# l2-l3.net
KiCad netlist of a schematic drawn in Altium Designer
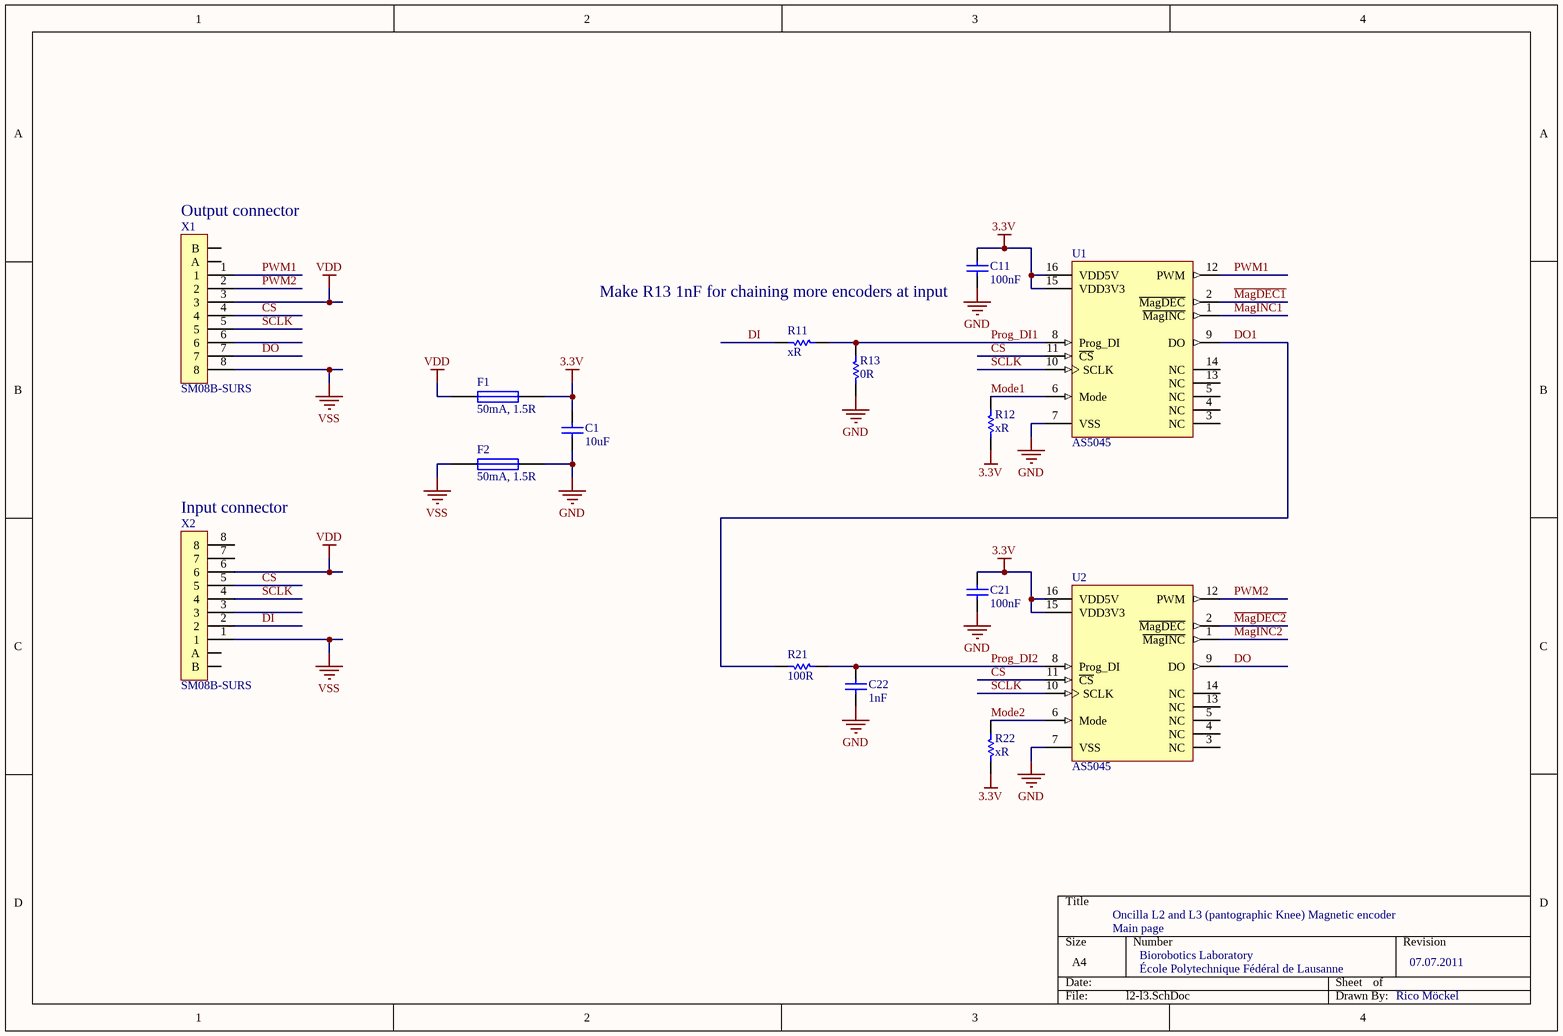
[diagram p0: l2-l3.SchDoc]

(export (version "E")
  (design (tool "Eeschema 10.0.6"))
  (components
    (comp (ref "C1")
      (value "10uF")
      (footprint "CAPC1608N")
      (description "Capacitor")
      (fields (field (name "PUBLISHER") "Altium Limited"))
      (libsource (lib "Miscellaneous Devices") (part "Cap"))
    )
    (comp (ref "C11")
      (value "100nF")
      (footprint "CAPC1005N")
      (description "Capacitor")
      (fields (field (name "PUBLISHER") "Altium Limited"))
      (libsource (lib "Miscellaneous Devices") (part "Cap"))
    )
    (comp (ref "C21")
      (value "100nF")
      (footprint "CAPC1005N")
      (description "Capacitor")
      (fields (field (name "PUBLISHER") "Altium Limited"))
      (libsource (lib "Miscellaneous Devices") (part "Cap"))
    )
    (comp (ref "C22")
      (value "1nF")
      (footprint "CAPC1005N")
      (description "Capacitor")
      (fields (field (name "PUBLISHER") "Altium Limited"))
      (libsource (lib "Miscellaneous Devices") (part "Cap"))
    )
    (comp (ref "F1")
      (value "50mA, 1.5R")
      (footprint "RESC1608N")
      (description "Ferrit Bead")
      (fields (field (name "PUBLISHER") "Altium Limited"))
      (libsource (lib "Miscellaneous Devices") (part "Fuse 1"))
    )
    (comp (ref "F2")
      (value "50mA, 1.5R")
      (footprint "RESC1608N")
      (description "Ferrit Bead")
      (fields (field (name "PUBLISHER") "Altium Limited"))
      (libsource (lib "Miscellaneous Devices") (part "Fuse 1"))
    )
    (comp (ref "R11")
      (value "xR")
      (footprint "RESC1005N")
      (description "Resistor")
      (fields (field (name "PUBLISHER") "Altium Limited"))
      (libsource (lib "") (part "Res1_1"))
    )
    (comp (ref "R12")
      (value "xR")
      (footprint "RESC1005N")
      (description "Resistor")
      (fields (field (name "PUBLISHER") "Altium Limited"))
      (libsource (lib "Miscellaneous Devices") (part "Res1"))
    )
    (comp (ref "R13")
      (value "0R")
      (footprint "RESC1005N")
      (description "Resistor")
      (fields (field (name "PUBLISHER") "Altium Limited"))
      (libsource (lib "Miscellaneous Devices") (part "Res1"))
    )
    (comp (ref "R21")
      (value "100R")
      (footprint "RESC1005N")
      (description "Resistor")
      (fields (field (name "PUBLISHER") "Altium Limited"))
      (libsource (lib "") (part "Res1_1"))
    )
    (comp (ref "R22")
      (value "xR")
      (footprint "RESC1005N")
      (description "Resistor")
      (fields (field (name "PUBLISHER") "Altium Limited"))
      (libsource (lib "Miscellaneous Devices") (part "Res1"))
    )
    (comp (ref "U1")
      (value "AS5045")
      (footprint "SSOP16")
      (description "12 Bit Programmable Magnetic Rotary Encoder")
      (libsource (lib "Roombots") (part "AS5045"))
    )
    (comp (ref "U2")
      (value "AS5045")
      (footprint "SSOP16")
      (description "12 Bit Programmable Magnetic Rotary Encoder")
      (libsource (lib "Roombots") (part "AS5045"))
    )
    (comp (ref "X1")
      (value "SM08B-SURS")
      (footprint "SM08B-SURS")
      (description "wire-to-board connector")
      (libsource (lib "") (part "SM08B-SURS_1"))
    )
    (comp (ref "X2")
      (value "SM08B-SURS")
      (footprint "SM08B-SURS")
      (description "wire-to-board connector")
      (libsource (lib "Roombots") (part "SM08B-SURS"))
    )
  )
  (nets
    (net (code "1") (name "/DI") (class "Default")
      (node (ref "R11") (pin "1") (pinfunction "1_1") (pintype "passive"))
      (node (ref "X2") (pin "2") (pinfunction "2_2") (pintype "passive"))
    )
    (net (code "2") (name "/DO") (class "Default")
      (node (ref "U2") (pin "9") (pinfunction "DO_9") (pintype "output"))
      (node (ref "X1") (pin "7") (pinfunction "7_7") (pintype "passive"))
    )
    (net (code "3") (name "/DO1") (class "Default")
      (node (ref "R21") (pin "1") (pinfunction "1_1") (pintype "passive"))
      (node (ref "U1") (pin "9") (pinfunction "DO_9") (pintype "output"))
    )
    (net (code "4") (name "/Mode1") (class "Default")
      (node (ref "R12") (pin "2") (pinfunction "2_2") (pintype "passive"))
      (node (ref "U1") (pin "6") (pinfunction "Mode_6") (pintype "input"))
    )
    (net (code "5") (name "/Mode2") (class "Default")
      (node (ref "R22") (pin "2") (pinfunction "2_2") (pintype "passive"))
      (node (ref "U2") (pin "6") (pinfunction "Mode_6") (pintype "input"))
    )
    (net (code "6") (name "/PWM1") (class "Default")
      (node (ref "U1") (pin "12") (pinfunction "PWM_12") (pintype "output"))
      (node (ref "X1") (pin "1") (pinfunction "1_1") (pintype "passive"))
    )
    (net (code "7") (name "/PWM2") (class "Default")
      (node (ref "U2") (pin "12") (pinfunction "PWM_12") (pintype "output"))
      (node (ref "X1") (pin "2") (pinfunction "2_2") (pintype "passive"))
    )
    (net (code "8") (name "/Prog_DI1") (class "Default")
      (node (ref "R11") (pin "2") (pinfunction "2_2") (pintype "passive"))
      (node (ref "R13") (pin "2") (pinfunction "2_2") (pintype "passive"))
      (node (ref "U1") (pin "8") (pinfunction "Prog_DI_8") (pintype "input"))
    )
    (net (code "9") (name "/Prog_DI2") (class "Default")
      (node (ref "C22") (pin "1") (pinfunction "1_1") (pintype "passive"))
      (node (ref "R21") (pin "2") (pinfunction "2_2") (pintype "passive"))
      (node (ref "U2") (pin "8") (pinfunction "Prog_DI_8") (pintype "input"))
    )
    (net (code "10") (name "/SCLK") (class "Default")
      (node (ref "U1") (pin "10") (pinfunction "SCLK_10") (pintype "input"))
      (node (ref "U2") (pin "10") (pinfunction "SCLK_10") (pintype "input"))
      (node (ref "X1") (pin "5") (pinfunction "5_5") (pintype "passive"))
      (node (ref "X2") (pin "4") (pinfunction "4_4") (pintype "passive"))
    )
    (net (code "11") (name "/~{CS}") (class "Default")
      (node (ref "U1") (pin "11") (pinfunction "~{CS}_11") (pintype "input"))
      (node (ref "U2") (pin "11") (pinfunction "~{CS}_11") (pintype "input"))
      (node (ref "X1") (pin "4") (pinfunction "4_4") (pintype "passive"))
      (node (ref "X2") (pin "5") (pinfunction "5_5") (pintype "passive"))
    )
    (net (code "12") (name "/~{MagDEC1}") (class "Default")
      (node (ref "U1") (pin "2") (pinfunction "~{MagDEC}_2") (pintype "output"))
    )
    (net (code "13") (name "/~{MagDEC2}") (class "Default")
      (node (ref "U2") (pin "2") (pinfunction "~{MagDEC}_2") (pintype "output"))
    )
    (net (code "14") (name "/~{MagINC1}") (class "Default")
      (node (ref "U1") (pin "1") (pinfunction "~{MagINC}_1") (pintype "output"))
    )
    (net (code "15") (name "/~{MagINC2}") (class "Default")
      (node (ref "U2") (pin "1") (pinfunction "~{MagINC}_1") (pintype "output"))
    )
    (net (code "16") (name "3.3V") (class "Default")
      (node (ref "C1") (pin "2") (pinfunction "2_2") (pintype "passive"))
      (node (ref "C11") (pin "1") (pinfunction "1_1") (pintype "passive"))
      (node (ref "C21") (pin "1") (pinfunction "1_1") (pintype "passive"))
      (node (ref "F1") (pin "2") (pinfunction "2_2") (pintype "passive"))
      (node (ref "R12") (pin "1") (pinfunction "1_1") (pintype "passive"))
      (node (ref "R22") (pin "1") (pinfunction "1_1") (pintype "passive"))
      (node (ref "U1") (pin "15") (pinfunction "VDD3V3_15") (pintype "power_in"))
      (node (ref "U1") (pin "16") (pinfunction "VDD5V_16") (pintype "power_in"))
      (node (ref "U2") (pin "15") (pinfunction "VDD3V3_15") (pintype "power_in"))
      (node (ref "U2") (pin "16") (pinfunction "VDD5V_16") (pintype "power_in"))
    )
    (net (code "17") (name "GND") (class "Default")
      (node (ref "C1") (pin "1") (pinfunction "1_1") (pintype "passive"))
      (node (ref "C11") (pin "2") (pinfunction "2_2") (pintype "passive"))
      (node (ref "C21") (pin "2") (pinfunction "2_2") (pintype "passive"))
      (node (ref "C22") (pin "2") (pinfunction "2_2") (pintype "passive"))
      (node (ref "F2") (pin "2") (pinfunction "2_2") (pintype "passive"))
      (node (ref "R13") (pin "1") (pinfunction "1_1") (pintype "passive"))
      (node (ref "U1") (pin "7") (pinfunction "VSS_7") (pintype "power_in"))
      (node (ref "U2") (pin "7") (pinfunction "VSS_7") (pintype "power_in"))
    )
    (net (code "18") (name "VDD") (class "Default")
      (node (ref "F1") (pin "1") (pinfunction "1_1") (pintype "passive"))
      (node (ref "X1") (pin "3") (pinfunction "3_3") (pintype "passive"))
      (node (ref "X2") (pin "6") (pinfunction "6_6") (pintype "passive"))
    )
    (net (code "19") (name "VSS") (class "Default")
      (node (ref "F2") (pin "1") (pinfunction "1_1") (pintype "passive"))
      (node (ref "X1") (pin "8") (pinfunction "8_8") (pintype "passive"))
      (node (ref "X2") (pin "1") (pinfunction "1_1") (pintype "passive"))
    )
    (net (code "20") (name "unconnected-(U1-NC-Pad3)") (class "Default")
      (node (ref "U1") (pin "3") (pinfunction "NC_3") (pintype "passive"))
    )
    (net (code "21") (name "unconnected-(U1-NC-Pad4)") (class "Default")
      (node (ref "U1") (pin "4") (pinfunction "NC_4") (pintype "passive"))
    )
    (net (code "22") (name "unconnected-(U1-NC-Pad5)") (class "Default")
      (node (ref "U1") (pin "5") (pinfunction "NC_5") (pintype "passive"))
    )
    (net (code "23") (name "unconnected-(U1-NC-Pad13)") (class "Default")
      (node (ref "U1") (pin "13") (pinfunction "NC_13") (pintype "passive"))
    )
    (net (code "24") (name "unconnected-(U1-NC-Pad14)") (class "Default")
      (node (ref "U1") (pin "14") (pinfunction "NC_14") (pintype "passive"))
    )
    (net (code "25") (name "unconnected-(U2-NC-Pad3)") (class "Default")
      (node (ref "U2") (pin "3") (pinfunction "NC_3") (pintype "passive"))
    )
    (net (code "26") (name "unconnected-(U2-NC-Pad4)") (class "Default")
      (node (ref "U2") (pin "4") (pinfunction "NC_4") (pintype "passive"))
    )
    (net (code "27") (name "unconnected-(U2-NC-Pad5)") (class "Default")
      (node (ref "U2") (pin "5") (pinfunction "NC_5") (pintype "passive"))
    )
    (net (code "28") (name "unconnected-(U2-NC-Pad13)") (class "Default")
      (node (ref "U2") (pin "13") (pinfunction "NC_13") (pintype "passive"))
    )
    (net (code "29") (name "unconnected-(U2-NC-Pad14)") (class "Default")
      (node (ref "U2") (pin "14") (pinfunction "NC_14") (pintype "passive"))
    )
    (net (code "30") (name "unconnected-(X1-Pad6)") (class "Default")
      (node (ref "X1") (pin "6") (pinfunction "6_6") (pintype "passive"))
    )
    (net (code "31") (name "unconnected-(X1-PadA)") (class "Default")
      (node (ref "X1") (pin "A") (pinfunction "A_A") (pintype "passive"))
    )
    (net (code "32") (name "unconnected-(X1-PadB)") (class "Default")
      (node (ref "X1") (pin "B") (pinfunction "B_B") (pintype "passive"))
    )
    (net (code "33") (name "unconnected-(X2-Pad3)") (class "Default")
      (node (ref "X2") (pin "3") (pinfunction "3_3") (pintype "passive"))
    )
    (net (code "34") (name "unconnected-(X2-Pad7)") (class "Default")
      (node (ref "X2") (pin "7") (pinfunction "7_7") (pintype "passive"))
    )
    (net (code "35") (name "unconnected-(X2-Pad8)") (class "Default")
      (node (ref "X2") (pin "8") (pinfunction "8_8") (pintype "passive"))
    )
    (net (code "36") (name "unconnected-(X2-PadA)") (class "Default")
      (node (ref "X2") (pin "A") (pinfunction "A_A") (pintype "passive"))
    )
    (net (code "37") (name "unconnected-(X2-PadB)") (class "Default")
      (node (ref "X2") (pin "B") (pinfunction "B_B") (pintype "passive"))
    )
  )
)
